# Solar-Charger-Board.net
KiCad netlist of a schematic drawn in EAGLE
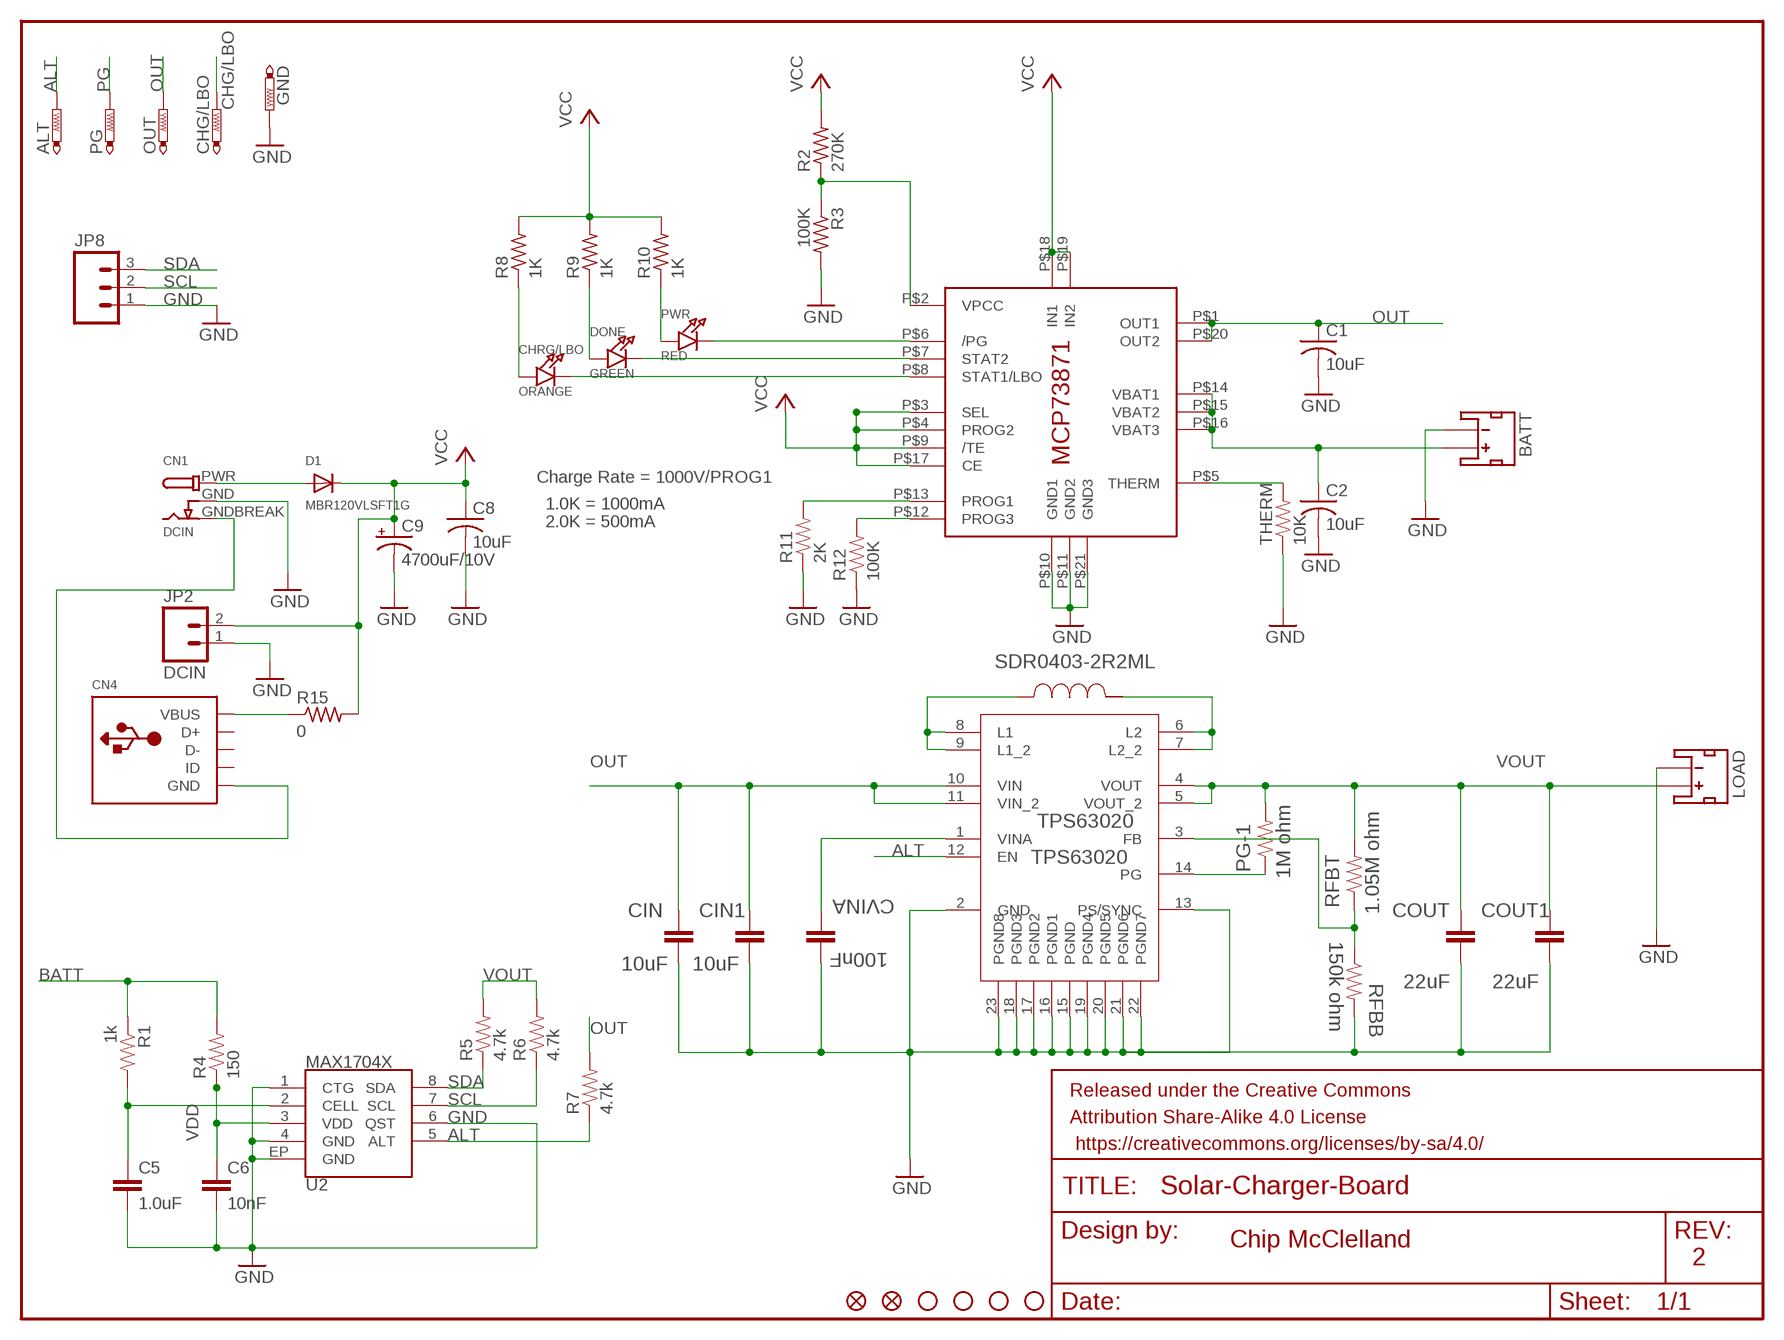
[diagram p0: schematic, sheet 1]

(export (version "E")
  (design (tool "Eeschema 10.0.6"))
  (components
    (comp (ref "ALT")
      (value "PTR1TP09R")
      (footprint "eagle-import:TP09R")
      (libsource (lib "eagle-import") (part "PTR1TP09R"))
    )
    (comp (ref "BATT")
      (value "JST_2MM_MALE")
      (footprint "eagle-import:JST-2-SMD")
      (libsource (lib "eagle-import") (part "JST_2MM_MALE"))
    )
    (comp (ref "C1")
      (value "10uF")
      (footprint "eagle-import:C0805K")
      (libsource (lib "eagle-import") (part "C-USC0805K"))
    )
    (comp (ref "C2")
      (value "10uF")
      (footprint "eagle-import:C0805K")
      (libsource (lib "eagle-import") (part "C-USC0805K"))
    )
    (comp (ref "C5")
      (value "1.0uF")
      (footprint "eagle-import:0805")
      (libsource (lib "eagle-import") (part "1.0UF-25V-+80/-20(0805)"))
    )
    (comp (ref "C6")
      (value "10nF")
      (footprint "eagle-import:0805")
      (libsource (lib "eagle-import") (part "2.2UF-25V-+80/-20(0805)"))
    )
    (comp (ref "C8")
      (value "10uF")
      (footprint "eagle-import:C0805K")
      (libsource (lib "eagle-import") (part "C-USC0805K"))
    )
    (comp (ref "C9")
      (value "4700uF/10V")
      (footprint "eagle-import:E5-13")
      (libsource (lib "eagle-import") (part "CPOL-USE5-13"))
    )
    (comp (ref "CHG/LBO")
      (value "PTR1TP09R")
      (footprint "eagle-import:TP09R")
      (libsource (lib "eagle-import") (part "PTR1TP09R"))
    )
    (comp (ref "CHRG/LBO")
      (value "ORANGE")
      (footprint "eagle-import:CHIPLED_0805_NOOUTLINE")
      (libsource (lib "eagle-import") (part "LED0805_NOOUTLINE"))
    )
    (comp (ref "CIN")
      (value "10uF")
      (footprint "eagle-import:0805")
      (libsource (lib "eagle-import") (part "CAP0805"))
    )
    (comp (ref "CIN1")
      (value "10uF")
      (footprint "eagle-import:0805")
      (libsource (lib "eagle-import") (part "CAP0805"))
    )
    (comp (ref "CN1")
      (value "DCIN")
      (footprint "eagle-import:DCJACK_2MM_SMT")
      (libsource (lib "eagle-import") (part "DCBARRELSMT"))
    )
    (comp (ref "CN4")
      (value "USBMINIBLARGE")
      (footprint "eagle-import:USB-MINIB_LARGER")
      (libsource (lib "eagle-import") (part "USBMINIBLARGE"))
    )
    (comp (ref "COUT")
      (value "22uF")
      (footprint "eagle-import:0805")
      (libsource (lib "eagle-import") (part "CAP0805"))
    )
    (comp (ref "COUT1")
      (value "22uF")
      (footprint "eagle-import:0805")
      (libsource (lib "eagle-import") (part "CAP0805"))
    )
    (comp (ref "CVINA")
      (value "100nF")
      (footprint "eagle-import:0805")
      (libsource (lib "eagle-import") (part "CAP0805"))
    )
    (comp (ref "D1")
      (value "MBR120VLSFT1G")
      (footprint "eagle-import:SOD-123")
      (libsource (lib "eagle-import") (part "DIODESOD-123"))
    )
    (comp (ref "DONE")
      (value "GREEN")
      (footprint "eagle-import:CHIPLED_0805_NOOUTLINE")
      (libsource (lib "eagle-import") (part "LED0805_NOOUTLINE"))
    )
    (comp (ref "FID1")
      (value "FIDUCIALUFIDUCIAL")
      (footprint "eagle-import:MICRO-FIDUCIAL")
      (libsource (lib "eagle-import") (part "FIDUCIALUFIDUCIAL"))
    )
    (comp (ref "FID2")
      (value "FIDUCIALUFIDUCIAL")
      (footprint "eagle-import:MICRO-FIDUCIAL")
      (libsource (lib "eagle-import") (part "FIDUCIALUFIDUCIAL"))
    )
    (comp (ref "FRAME2")
      (value "FRAME-LETTER")
      (footprint "eagle-import:CREATIVE_COMMONS")
      (libsource (lib "eagle-import") (part "FRAME-LETTER"))
    )
    (comp (ref "GND")
      (value "PTR1TP09R")
      (footprint "eagle-import:TP09R")
      (libsource (lib "eagle-import") (part "PTR1TP09R"))
    )
    (comp (ref "JP2")
      (value "DCIN")
      (footprint "eagle-import:1X02_LOCK")
      (libsource (lib "eagle-import") (part "M02LOCK"))
    )
    (comp (ref "JP3")
      (value "STAND-OFF")
      (footprint "eagle-import:STAND-OFF")
      (libsource (lib "eagle-import") (part "STAND-OFF"))
    )
    (comp (ref "JP4")
      (value "STAND-OFF")
      (footprint "eagle-import:STAND-OFF")
      (libsource (lib "eagle-import") (part "STAND-OFF"))
    )
    (comp (ref "JP5")
      (value "STAND-OFF")
      (footprint "eagle-import:STAND-OFF")
      (libsource (lib "eagle-import") (part "STAND-OFF"))
    )
    (comp (ref "JP6")
      (value "STAND-OFF")
      (footprint "eagle-import:STAND-OFF")
      (libsource (lib "eagle-import") (part "STAND-OFF"))
    )
    (comp (ref "JP8")
      (value "M03LOCK")
      (footprint "eagle-import:1X03_LOCK")
      (libsource (lib "eagle-import") (part "M03LOCK"))
    )
    (comp (ref "L1")
      (value "SDR0403-2R2ML")
      (footprint "eagle-import:SDR0403")
      (libsource (lib "eagle-import") (part "SDR0403-2R2ML"))
    )
    (comp (ref "LOAD")
      (value "JST_2MM_MALE")
      (footprint "eagle-import:JST-2-SMD")
      (libsource (lib "eagle-import") (part "JST_2MM_MALE"))
    )
    (comp (ref "MAX1704X")
      (value "U2")
      (footprint "eagle-import:TDFN-8")
      (libsource (lib "eagle-import") (part "MAX1704X"))
    )
    (comp (ref "MCP73871")
      (value "U1")
      (footprint "eagle-import:QFN20_4MM")
      (libsource (lib "eagle-import") (part "MCP73871"))
    )
    (comp (ref "OUT")
      (value "PTR1TP09R")
      (footprint "eagle-import:TP09R")
      (libsource (lib "eagle-import") (part "PTR1TP09R"))
    )
    (comp (ref "PG")
      (value "PTR1TP09R")
      (footprint "eagle-import:TP09R")
      (libsource (lib "eagle-import") (part "PTR1TP09R"))
    )
    (comp (ref "PG-1")
      (value "1M ohm")
      (footprint "eagle-import:0805")
      (libsource (lib "eagle-import") (part "RESISTOR0805-RES"))
    )
    (comp (ref "PWR")
      (value "RED")
      (footprint "eagle-import:CHIPLED_0805_NOOUTLINE")
      (libsource (lib "eagle-import") (part "LED0805_NOOUTLINE"))
    )
    (comp (ref "R1")
      (value "1k")
      (footprint "eagle-import:0805")
      (libsource (lib "eagle-import") (part "RESISTOR0805-RES"))
    )
    (comp (ref "R2")
      (value "270K")
      (footprint "eagle-import:R0805")
      (libsource (lib "eagle-import") (part "R-US_R0805"))
    )
    (comp (ref "R3")
      (value "100K")
      (footprint "eagle-import:R0805")
      (libsource (lib "eagle-import") (part "R-US_R0805"))
    )
    (comp (ref "R4")
      (value "150")
      (footprint "eagle-import:0805")
      (libsource (lib "eagle-import") (part "RESISTOR0805-RES"))
    )
    (comp (ref "R5")
      (value "4.7k")
      (footprint "eagle-import:0805")
      (libsource (lib "eagle-import") (part "RESISTOR0805-RES"))
    )
    (comp (ref "R6")
      (value "4.7k")
      (footprint "eagle-import:0805")
      (libsource (lib "eagle-import") (part "RESISTOR0805-RES"))
    )
    (comp (ref "R7")
      (value "4.7k")
      (footprint "eagle-import:0805")
      (libsource (lib "eagle-import") (part "RESISTOR0805-RES"))
    )
    (comp (ref "R8")
      (value "1K")
      (footprint "eagle-import:R0805")
      (libsource (lib "eagle-import") (part "R-US_R0805"))
    )
    (comp (ref "R9")
      (value "1K")
      (footprint "eagle-import:R0805")
      (libsource (lib "eagle-import") (part "R-US_R0805"))
    )
    (comp (ref "R10")
      (value "1K")
      (footprint "eagle-import:R0805")
      (libsource (lib "eagle-import") (part "R-US_R0805"))
    )
    (comp (ref "R11")
      (value "2K")
      (footprint "eagle-import:0805")
      (libsource (lib "eagle-import") (part "RESISTOR0805-RES"))
    )
    (comp (ref "R12")
      (value "100K")
      (footprint "eagle-import:0805")
      (libsource (lib "eagle-import") (part "RESISTOR0805-RES"))
    )
    (comp (ref "R15")
      (value "0")
      (footprint "eagle-import:R0805")
      (libsource (lib "eagle-import") (part "R-US_R0805"))
    )
    (comp (ref "RFBB")
      (value "150k ohm")
      (footprint "eagle-import:0805")
      (libsource (lib "eagle-import") (part "RESISTOR0805-RES"))
    )
    (comp (ref "RFBT")
      (value "1.05M ohm")
      (footprint "eagle-import:0805")
      (libsource (lib "eagle-import") (part "RESISTOR0805-RES"))
    )
    (comp (ref "THERM")
      (value "10K")
      (footprint "eagle-import:0805")
      (libsource (lib "eagle-import") (part "RESISTOR0805-RES"))
    )
    (comp (ref "TPS63020")
      (value "TPS63020")
      (footprint "eagle-import:QFN14-3X4MM")
      (libsource (lib "eagle-import") (part "TPS63020"))
    )
  )
  (nets
    (net (code "1") (name "/ALT") (class "Default")
      (node (ref "ALT") (pin "TP") (pinfunction "TP_TP") (pintype "input"))
      (node (ref "MAX1704X") (pin "5") (pinfunction "ALT_5") (pintype "bidirectional"))
      (node (ref "R7") (pin "1") (pinfunction "1_1") (pintype "passive"))
      (node (ref "TPS63020") (pin "12") (pinfunction "EN_12") (pintype "bidirectional"))
    )
    (net (code "2") (name "/BATT") (class "Default")
      (node (ref "BATT") (pin "2") (pinfunction "+_2") (pintype "bidirectional"))
      (node (ref "C2") (pin "1") (pinfunction "1_1") (pintype "passive"))
      (node (ref "MCP73871") (pin "P$14") (pinfunction "VBAT1_P$14") (pintype "output"))
      (node (ref "MCP73871") (pin "P$15") (pinfunction "VBAT2_P$15") (pintype "output"))
      (node (ref "MCP73871") (pin "P$16") (pinfunction "VBAT3_P$16") (pintype "output"))
      (node (ref "R1") (pin "1") (pinfunction "1_1") (pintype "passive"))
      (node (ref "R4") (pin "2") (pinfunction "2_2") (pintype "passive"))
    )
    (net (code "3") (name "/CHG{slash}LBO") (class "Default")
      (node (ref "CHG/LBO") (pin "TP") (pinfunction "TP_TP") (pintype "input"))
      (node (ref "CHRG/LBO") (pin "C") (pinfunction "C_C") (pintype "passive"))
      (node (ref "MCP73871") (pin "P$8") (pinfunction "STAT1/LBO_P$8") (pintype "output"))
    )
    (net (code "4") (name "/OUT") (class "Default")
      (node (ref "C1") (pin "1") (pinfunction "1_1") (pintype "passive"))
      (node (ref "CIN") (pin "1") (pinfunction "1_1") (pintype "passive"))
      (node (ref "CIN1") (pin "1") (pinfunction "1_1") (pintype "passive"))
      (node (ref "MCP73871") (pin "P$1") (pinfunction "OUT1_P$1") (pintype "output"))
      (node (ref "MCP73871") (pin "P$20") (pinfunction "OUT2_P$20") (pintype "output"))
      (node (ref "OUT") (pin "TP") (pinfunction "TP_TP") (pintype "input"))
      (node (ref "R7") (pin "2") (pinfunction "2_2") (pintype "passive"))
      (node (ref "TPS63020") (pin "10") (pinfunction "VIN_10") (pintype "bidirectional"))
      (node (ref "TPS63020") (pin "11") (pinfunction "VIN_2_11") (pintype "bidirectional"))
    )
    (net (code "5") (name "/PG") (class "Default")
      (node (ref "PG") (pin "TP") (pinfunction "TP_TP") (pintype "input"))
      (node (ref "PG-1") (pin "1") (pinfunction "1_1") (pintype "passive"))
      (node (ref "TPS63020") (pin "14") (pinfunction "PG_14") (pintype "bidirectional"))
    )
    (net (code "6") (name "/SCL") (class "Default")
      (node (ref "JP8") (pin "2") (pinfunction "2_2") (pintype "passive"))
      (node (ref "MAX1704X") (pin "7") (pinfunction "SCL_7") (pintype "bidirectional"))
      (node (ref "R6") (pin "1") (pinfunction "1_1") (pintype "passive"))
    )
    (net (code "7") (name "/SDA") (class "Default")
      (node (ref "JP8") (pin "3") (pinfunction "3_3") (pintype "passive"))
      (node (ref "MAX1704X") (pin "8") (pinfunction "SDA_8") (pintype "bidirectional"))
      (node (ref "R5") (pin "1") (pinfunction "1_1") (pintype "passive"))
    )
    (net (code "8") (name "/VDD") (class "Default")
      (node (ref "C6") (pin "1") (pinfunction "1_1") (pintype "passive"))
      (node (ref "MAX1704X") (pin "3") (pinfunction "VDD_3") (pintype "bidirectional"))
      (node (ref "R4") (pin "1") (pinfunction "1_1") (pintype "passive"))
    )
    (net (code "9") (name "/VOUT") (class "Default")
      (node (ref "COUT") (pin "1") (pinfunction "1_1") (pintype "passive"))
      (node (ref "COUT1") (pin "1") (pinfunction "1_1") (pintype "passive"))
      (node (ref "LOAD") (pin "2") (pinfunction "+_2") (pintype "bidirectional"))
      (node (ref "PG-1") (pin "2") (pinfunction "2_2") (pintype "passive"))
      (node (ref "R5") (pin "2") (pinfunction "2_2") (pintype "passive"))
      (node (ref "R6") (pin "2") (pinfunction "2_2") (pintype "passive"))
      (node (ref "RFBT") (pin "2") (pinfunction "2_2") (pintype "passive"))
      (node (ref "TPS63020") (pin "4") (pinfunction "VOUT_4") (pintype "bidirectional"))
      (node (ref "TPS63020") (pin "5") (pinfunction "VOUT_2_5") (pintype "bidirectional"))
    )
    (net (code "10") (name "GND") (class "Default")
      (node (ref "BATT") (pin "1") (pinfunction "-_1") (pintype "bidirectional"))
      (node (ref "C1") (pin "2") (pinfunction "2_2") (pintype "passive"))
      (node (ref "C2") (pin "2") (pinfunction "2_2") (pintype "passive"))
      (node (ref "C5") (pin "2") (pinfunction "2_2") (pintype "passive"))
      (node (ref "C6") (pin "2") (pinfunction "2_2") (pintype "passive"))
      (node (ref "C8") (pin "2") (pinfunction "2_2") (pintype "passive"))
      (node (ref "C9") (pin "-") (pinfunction "-_-") (pintype "passive"))
      (node (ref "CIN") (pin "2") (pinfunction "2_2") (pintype "passive"))
      (node (ref "CIN1") (pin "2") (pinfunction "2_2") (pintype "passive"))
      (node (ref "CN1") (pin "GND") (pinfunction "GNDBREAK_GND") (pintype "power_in"))
      (node (ref "COUT") (pin "2") (pinfunction "2_2") (pintype "passive"))
      (node (ref "COUT1") (pin "2") (pinfunction "2_2") (pintype "passive"))
      (node (ref "CVINA") (pin "2") (pinfunction "2_2") (pintype "passive"))
      (node (ref "GND") (pin "TP") (pinfunction "TP_TP") (pintype "input"))
      (node (ref "JP2") (pin "1") (pinfunction "1_1") (pintype "passive"))
      (node (ref "JP8") (pin "1") (pinfunction "1_1") (pintype "passive"))
      (node (ref "LOAD") (pin "1") (pinfunction "-_1") (pintype "bidirectional"))
      (node (ref "MAX1704X") (pin "1") (pinfunction "CTG_1") (pintype "bidirectional"))
      (node (ref "MAX1704X") (pin "4") (pinfunction "GND_4") (pintype "bidirectional"))
      (node (ref "MAX1704X") (pin "6") (pinfunction "QST_6") (pintype "bidirectional"))
      (node (ref "MAX1704X") (pin "EP") (pinfunction "GND_EP") (pintype "bidirectional"))
      (node (ref "MCP73871") (pin "P$10") (pinfunction "GND1_P$10") (pintype "power_in"))
      (node (ref "MCP73871") (pin "P$11") (pinfunction "GND2_P$11") (pintype "power_in"))
      (node (ref "MCP73871") (pin "P$21") (pinfunction "GND3_P$21") (pintype "power_in"))
      (node (ref "R11") (pin "1") (pinfunction "1_1") (pintype "passive"))
      (node (ref "R12") (pin "1") (pinfunction "1_1") (pintype "passive"))
      (node (ref "R3") (pin "2") (pinfunction "2_2") (pintype "passive"))
      (node (ref "RFBB") (pin "2") (pinfunction "2_2") (pintype "passive"))
      (node (ref "THERM") (pin "1") (pinfunction "1_1") (pintype "passive"))
      (node (ref "TPS63020") (pin "13") (pinfunction "PS/SYNC_13") (pintype "bidirectional"))
      (node (ref "TPS63020") (pin "15") (pinfunction "PGND_15") (pintype "bidirectional"))
      (node (ref "TPS63020") (pin "16") (pinfunction "PGND1_16") (pintype "bidirectional"))
      (node (ref "TPS63020") (pin "17") (pinfunction "PGND2_17") (pintype "bidirectional"))
      (node (ref "TPS63020") (pin "18") (pinfunction "PGND3_18") (pintype "bidirectional"))
      (node (ref "TPS63020") (pin "19") (pinfunction "PGND4_19") (pintype "bidirectional"))
      (node (ref "TPS63020") (pin "2") (pinfunction "GND_2") (pintype "bidirectional"))
      (node (ref "TPS63020") (pin "20") (pinfunction "PGND5_20") (pintype "bidirectional"))
      (node (ref "TPS63020") (pin "21") (pinfunction "PGND6_21") (pintype "bidirectional"))
      (node (ref "TPS63020") (pin "22") (pinfunction "PGND7_22") (pintype "bidirectional"))
      (node (ref "TPS63020") (pin "23") (pinfunction "PGND8_23") (pintype "bidirectional"))
    )
    (net (code "11") (name "Net-(CHRG/LBO-PadA)") (class "Default")
      (node (ref "CHRG/LBO") (pin "A") (pinfunction "A_A") (pintype "passive"))
      (node (ref "R8") (pin "1") (pinfunction "1_1") (pintype "passive"))
    )
    (net (code "12") (name "Net-(CN1-GND)") (class "Default")
      (node (ref "CN1") (pin "GNDBREAK") (pinfunction "GND_GNDBREAK") (pintype "power_in"))
      (node (ref "CN4") (pin "GND") (pinfunction "GND_GND") (pintype "power_in"))
      (node (ref "CN4") (pin "GND1") (pinfunction "GND_GND1") (pintype "power_in"))
      (node (ref "CN4") (pin "GND2") (pinfunction "GND_GND2") (pintype "power_in"))
      (node (ref "CN4") (pin "GND3") (pinfunction "GND_GND3") (pintype "power_in"))
      (node (ref "CN4") (pin "GND4") (pinfunction "GND_GND4") (pintype "power_in"))
    )
    (net (code "13") (name "Net-(CN1-PadPWR)") (class "Default")
      (node (ref "CN1") (pin "PWR") (pinfunction "PWR_PWR") (pintype "power_in"))
      (node (ref "D1") (pin "A") (pinfunction "A_A") (pintype "passive"))
    )
    (net (code "14") (name "Net-(CN4-PadVBUS)") (class "Default")
      (node (ref "CN4") (pin "VBUS") (pinfunction "VBUS_VBUS") (pintype "power_in"))
      (node (ref "R15") (pin "1") (pinfunction "1_1") (pintype "passive"))
    )
    (net (code "15") (name "Net-(DONE-PadA)") (class "Default")
      (node (ref "DONE") (pin "A") (pinfunction "A_A") (pintype "passive"))
      (node (ref "R9") (pin "1") (pinfunction "1_1") (pintype "passive"))
    )
    (net (code "16") (name "Net-(MAX1704X-CELL)") (class "Default")
      (node (ref "C5") (pin "1") (pinfunction "1_1") (pintype "passive"))
      (node (ref "MAX1704X") (pin "2") (pinfunction "CELL_2") (pintype "bidirectional"))
      (node (ref "R1") (pin "2") (pinfunction "2_2") (pintype "passive"))
    )
    (net (code "17") (name "Net-(MCP73871-PROG1)") (class "Default")
      (node (ref "MCP73871") (pin "P$13") (pinfunction "PROG1_P$13") (pintype "input"))
      (node (ref "R11") (pin "2") (pinfunction "2_2") (pintype "passive"))
    )
    (net (code "18") (name "Net-(MCP73871-PROG3)") (class "Default")
      (node (ref "MCP73871") (pin "P$12") (pinfunction "PROG3_P$12") (pintype "input"))
      (node (ref "R12") (pin "2") (pinfunction "2_2") (pintype "passive"))
    )
    (net (code "19") (name "Net-(MCP73871-STAT2)") (class "Default")
      (node (ref "DONE") (pin "C") (pinfunction "C_C") (pintype "passive"))
      (node (ref "MCP73871") (pin "P$7") (pinfunction "STAT2_P$7") (pintype "output"))
    )
    (net (code "20") (name "Net-(MCP73871-THERM)") (class "Default")
      (node (ref "MCP73871") (pin "P$5") (pinfunction "THERM_P$5") (pintype "input"))
      (node (ref "THERM") (pin "2") (pinfunction "2_2") (pintype "passive"))
    )
    (net (code "21") (name "Net-(MCP73871-VPCC)") (class "Default")
      (node (ref "MCP73871") (pin "P$2") (pinfunction "VPCC_P$2") (pintype "input"))
      (node (ref "R2") (pin "1") (pinfunction "1_1") (pintype "passive"))
      (node (ref "R3") (pin "1") (pinfunction "1_1") (pintype "passive"))
    )
    (net (code "22") (name "Net-(MCP73871-{slash}PG)") (class "Default")
      (node (ref "MCP73871") (pin "P$6") (pinfunction "/PG_P$6") (pintype "output"))
      (node (ref "PWR") (pin "C") (pinfunction "C_C") (pintype "passive"))
    )
    (net (code "23") (name "Net-(PWR-PadA)") (class "Default")
      (node (ref "PWR") (pin "A") (pinfunction "A_A") (pintype "passive"))
      (node (ref "R10") (pin "1") (pinfunction "1_1") (pintype "passive"))
    )
    (net (code "24") (name "Net-(TPS63020-FB)") (class "Default")
      (node (ref "RFBB") (pin "1") (pinfunction "1_1") (pintype "passive"))
      (node (ref "RFBT") (pin "1") (pinfunction "1_1") (pintype "passive"))
      (node (ref "TPS63020") (pin "3") (pinfunction "FB_3") (pintype "bidirectional"))
    )
    (net (code "25") (name "Net-(TPS63020-L1)") (class "Default")
      (node (ref "L1") (pin "1") (pinfunction "1_1") (pintype "passive"))
      (node (ref "TPS63020") (pin "8") (pinfunction "L1_8") (pintype "bidirectional"))
      (node (ref "TPS63020") (pin "9") (pinfunction "L1_2_9") (pintype "bidirectional"))
    )
    (net (code "26") (name "Net-(TPS63020-L2)") (class "Default")
      (node (ref "L1") (pin "2") (pinfunction "2_2") (pintype "passive"))
      (node (ref "TPS63020") (pin "6") (pinfunction "L2_6") (pintype "bidirectional"))
      (node (ref "TPS63020") (pin "7") (pinfunction "L2_2_7") (pintype "bidirectional"))
    )
    (net (code "27") (name "Net-(TPS63020-VINA)") (class "Default")
      (node (ref "CVINA") (pin "1") (pinfunction "1_1") (pintype "passive"))
      (node (ref "TPS63020") (pin "1") (pinfunction "VINA_1") (pintype "bidirectional"))
    )
    (net (code "28") (name "VCC") (class "Default")
      (node (ref "C8") (pin "1") (pinfunction "1_1") (pintype "passive"))
      (node (ref "C9") (pin "+") (pinfunction "+_+") (pintype "passive"))
      (node (ref "D1") (pin "C") (pinfunction "C_C") (pintype "passive"))
      (node (ref "JP2") (pin "2") (pinfunction "2_2") (pintype "passive"))
      (node (ref "MCP73871") (pin "P$17") (pinfunction "CE_P$17") (pintype "input"))
      (node (ref "MCP73871") (pin "P$18") (pinfunction "IN1_P$18") (pintype "input"))
      (node (ref "MCP73871") (pin "P$19") (pinfunction "IN2_P$19") (pintype "input"))
      (node (ref "MCP73871") (pin "P$3") (pinfunction "SEL_P$3") (pintype "input"))
      (node (ref "MCP73871") (pin "P$4") (pinfunction "PROG2_P$4") (pintype "input"))
      (node (ref "MCP73871") (pin "P$9") (pinfunction "/TE_P$9") (pintype "input"))
      (node (ref "R10") (pin "2") (pinfunction "2_2") (pintype "passive"))
      (node (ref "R15") (pin "2") (pinfunction "2_2") (pintype "passive"))
      (node (ref "R2") (pin "2") (pinfunction "2_2") (pintype "passive"))
      (node (ref "R8") (pin "2") (pinfunction "2_2") (pintype "passive"))
      (node (ref "R9") (pin "2") (pinfunction "2_2") (pintype "passive"))
    )
    (net (code "29") (name "unconnected-(BATT-PAD1-PadNC1)") (class "Default")
      (node (ref "BATT") (pin "NC1") (pinfunction "PAD1_NC1") (pintype "bidirectional"))
    )
    (net (code "30") (name "unconnected-(BATT-PAD2-PadNC2)") (class "Default")
      (node (ref "BATT") (pin "NC2") (pinfunction "PAD2_NC2") (pintype "bidirectional"))
    )
    (net (code "31") (name "unconnected-(CN4-PadD+)") (class "Default")
      (node (ref "CN4") (pin "D+") (pinfunction "D+_D+") (pintype "bidirectional"))
    )
    (net (code "32") (name "unconnected-(CN4-PadD-)") (class "Default")
      (node (ref "CN4") (pin "D-") (pinfunction "D-_D-") (pintype "bidirectional"))
    )
    (net (code "33") (name "unconnected-(CN4-PadID)") (class "Default")
      (node (ref "CN4") (pin "ID") (pinfunction "ID_ID") (pintype "bidirectional"))
    )
    (net (code "34") (name "unconnected-(LOAD-PAD1-PadNC1)") (class "Default")
      (node (ref "LOAD") (pin "NC1") (pinfunction "PAD1_NC1") (pintype "bidirectional"))
    )
    (net (code "35") (name "unconnected-(LOAD-PAD2-PadNC2)") (class "Default")
      (node (ref "LOAD") (pin "NC2") (pinfunction "PAD2_NC2") (pintype "bidirectional"))
    )
  )
)
